# 11_RCL.net
KiCad netlist of a schematic drawn in EAGLE
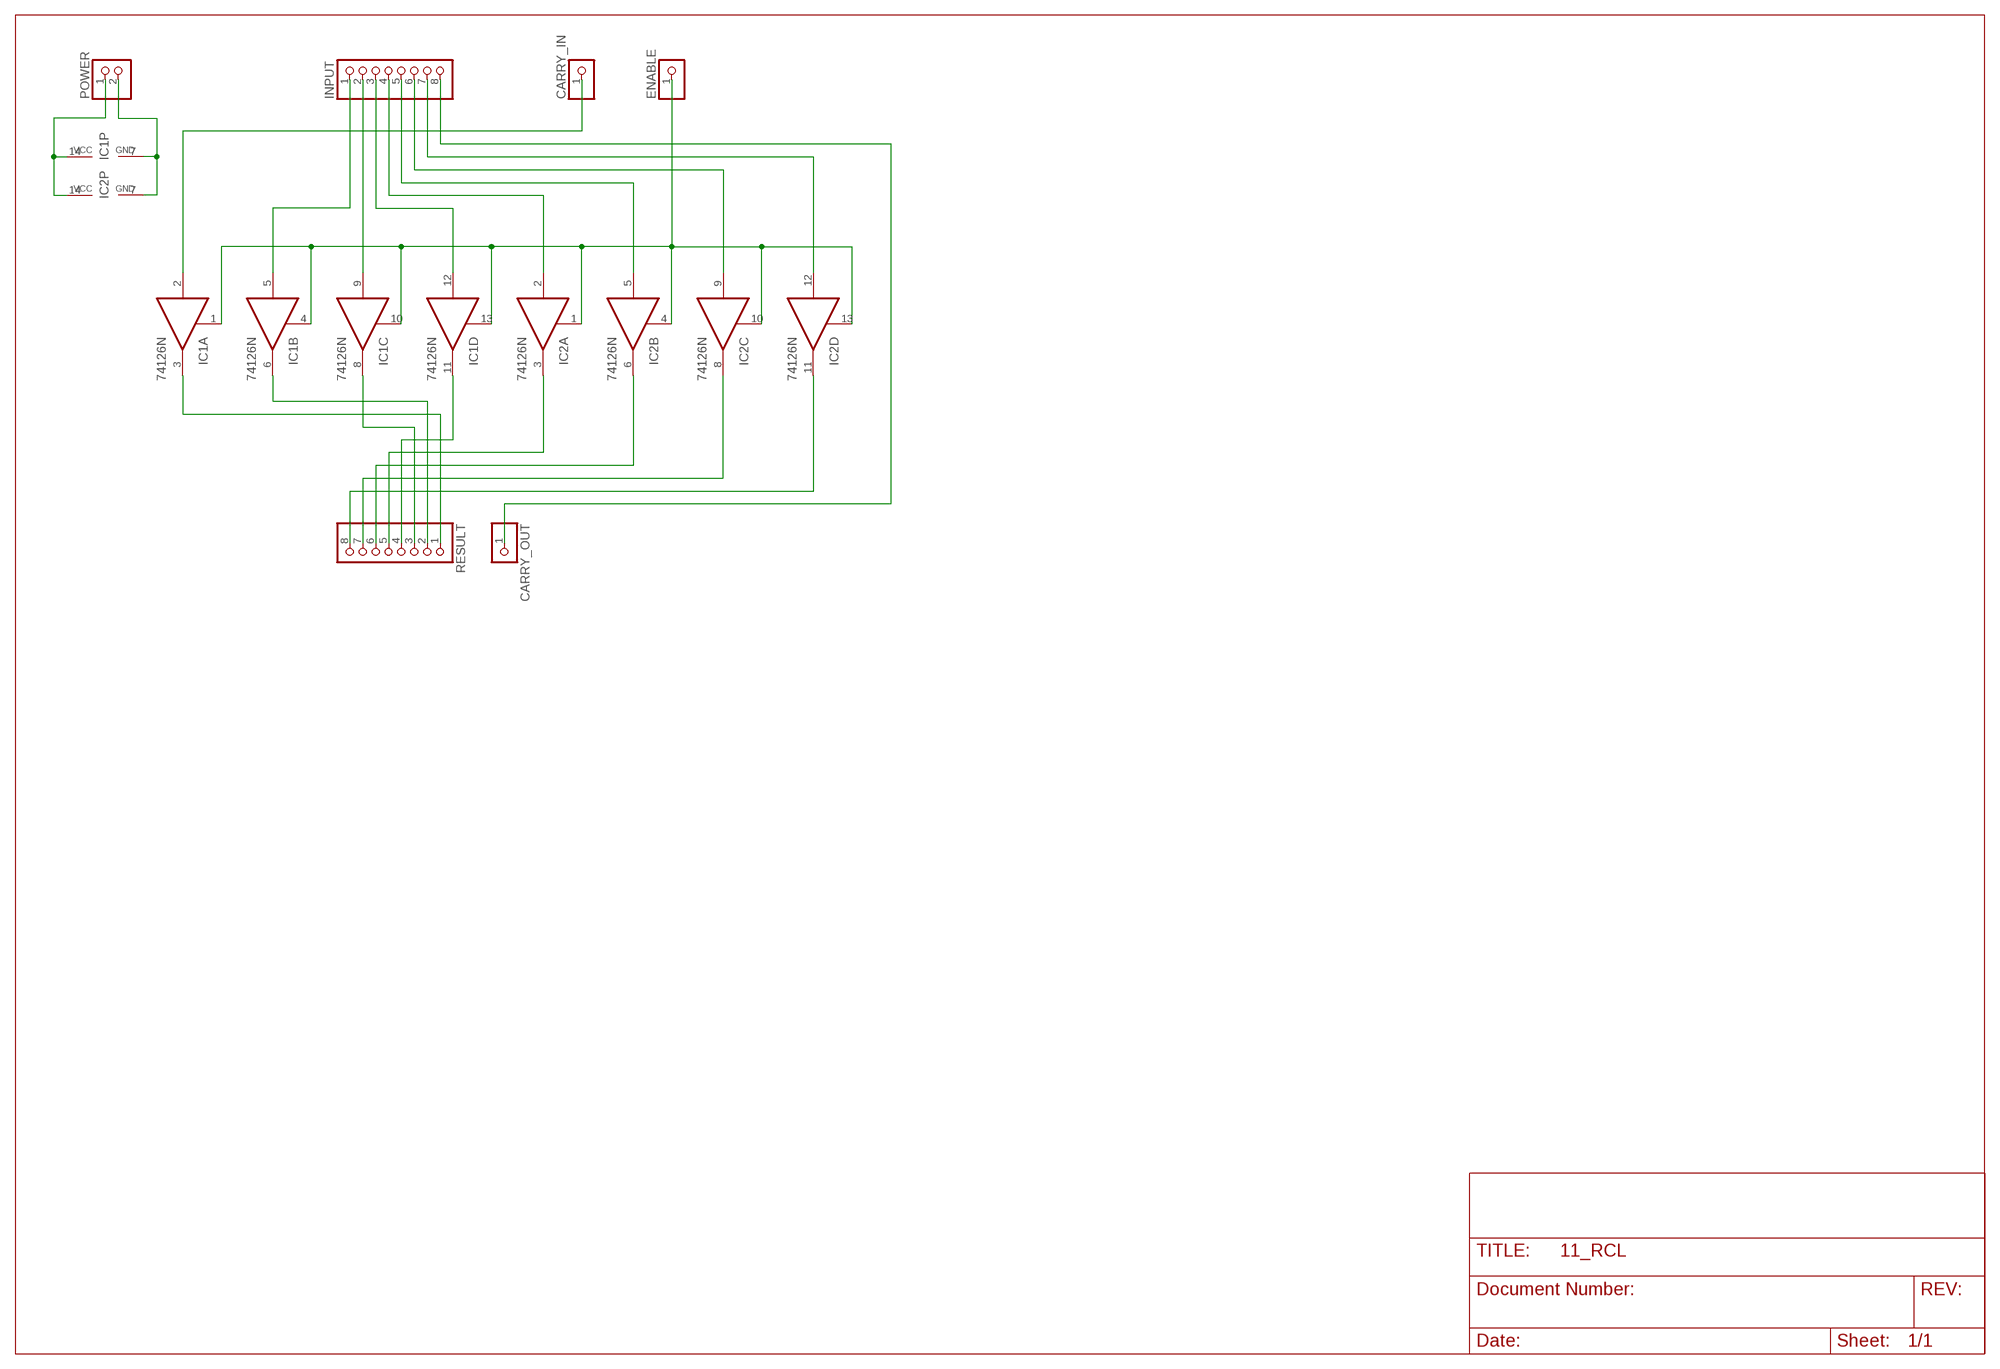
[diagram p0: schematic, sheet 1]

(export (version "E")
  (design (tool "Eeschema 10.0.6"))
  (components
    (comp (ref "CARRY_IN")
      (value "PINHD-1X1")
      (footprint "eagle-import:1X01")
      (libsource (lib "eagle-import") (part "PINHD-1X1"))
    )
    (comp (ref "CARRY_OUT")
      (value "PINHD-1X1")
      (footprint "eagle-import:1X01")
      (libsource (lib "eagle-import") (part "PINHD-1X1"))
    )
    (comp (ref "ENABLE")
      (value "PINHD-1X1")
      (footprint "eagle-import:1X01")
      (libsource (lib "eagle-import") (part "PINHD-1X1"))
    )
    (comp (ref "IC1")
      (value "74126N")
      (footprint "eagle-import:DIL14")
      (libsource (lib "eagle-import") (part "74126N"))
    )
    (comp (ref "IC2")
      (value "74126N")
      (footprint "eagle-import:DIL14")
      (libsource (lib "eagle-import") (part "74126N"))
    )
    (comp (ref "INPUT")
      (value "PINHD-1X8")
      (footprint "eagle-import:1X08")
      (libsource (lib "eagle-import") (part "PINHD-1X8"))
    )
    (comp (ref "POWER")
      (value "PINHD-1X2")
      (footprint "eagle-import:1X02")
      (libsource (lib "eagle-import") (part "PINHD-1X2"))
    )
    (comp (ref "RESULT")
      (value "PINHD-1X8")
      (footprint "eagle-import:1X08")
      (libsource (lib "eagle-import") (part "PINHD-1X8"))
    )
  )
  (nets
    (net (code "1") (name "Net-(CARRY_OUT-Pad1)") (class "Default")
      (node (ref "CARRY_OUT") (pin "1") (pinfunction "1_1") (pintype "passive"))
      (node (ref "INPUT") (pin "8") (pinfunction "8_8") (pintype "passive"))
    )
    (net (code "2") (name "Net-(IC1A-I)") (class "Default")
      (node (ref "CARRY_IN") (pin "1") (pinfunction "1_1") (pintype "passive"))
      (node (ref "IC1") (pin "2") (pinfunction "I_2") (pintype "input"))
    )
    (net (code "3") (name "Net-(IC1A-O)") (class "Default")
      (node (ref "IC1") (pin "3") (pinfunction "O_3") (pintype "output"))
      (node (ref "RESULT") (pin "1") (pinfunction "1_1") (pintype "passive"))
    )
    (net (code "4") (name "Net-(IC1A-OE)") (class "Default")
      (node (ref "ENABLE") (pin "1") (pinfunction "1_1") (pintype "passive"))
      (node (ref "IC1") (pin "1") (pinfunction "OE_1") (pintype "input"))
      (node (ref "IC1") (pin "10") (pinfunction "OE_10") (pintype "input"))
      (node (ref "IC1") (pin "13") (pinfunction "OE_13") (pintype "input"))
      (node (ref "IC1") (pin "4") (pinfunction "OE_4") (pintype "input"))
      (node (ref "IC2") (pin "1") (pinfunction "OE_1") (pintype "input"))
      (node (ref "IC2") (pin "10") (pinfunction "OE_10") (pintype "input"))
      (node (ref "IC2") (pin "13") (pinfunction "OE_13") (pintype "input"))
      (node (ref "IC2") (pin "4") (pinfunction "OE_4") (pintype "input"))
    )
    (net (code "5") (name "Net-(IC1B-I)") (class "Default")
      (node (ref "IC1") (pin "5") (pinfunction "I_5") (pintype "input"))
      (node (ref "INPUT") (pin "1") (pinfunction "1_1") (pintype "passive"))
    )
    (net (code "6") (name "Net-(IC1B-O)") (class "Default")
      (node (ref "IC1") (pin "6") (pinfunction "O_6") (pintype "output"))
      (node (ref "RESULT") (pin "2") (pinfunction "2_2") (pintype "passive"))
    )
    (net (code "7") (name "Net-(IC1C-I)") (class "Default")
      (node (ref "IC1") (pin "9") (pinfunction "I_9") (pintype "input"))
      (node (ref "INPUT") (pin "2") (pinfunction "2_2") (pintype "passive"))
    )
    (net (code "8") (name "Net-(IC1C-O)") (class "Default")
      (node (ref "IC1") (pin "8") (pinfunction "O_8") (pintype "output"))
      (node (ref "RESULT") (pin "3") (pinfunction "3_3") (pintype "passive"))
    )
    (net (code "9") (name "Net-(IC1D-I)") (class "Default")
      (node (ref "IC1") (pin "12") (pinfunction "I_12") (pintype "input"))
      (node (ref "INPUT") (pin "3") (pinfunction "3_3") (pintype "passive"))
    )
    (net (code "10") (name "Net-(IC1D-O)") (class "Default")
      (node (ref "IC1") (pin "11") (pinfunction "O_11") (pintype "output"))
      (node (ref "RESULT") (pin "4") (pinfunction "4_4") (pintype "passive"))
    )
    (net (code "11") (name "Net-(IC1E-GND)") (class "Default")
      (node (ref "IC1") (pin "7") (pinfunction "GND_7") (pintype "power_in"))
      (node (ref "IC2") (pin "7") (pinfunction "GND_7") (pintype "power_in"))
      (node (ref "POWER") (pin "2") (pinfunction "2_2") (pintype "passive"))
    )
    (net (code "12") (name "Net-(IC1E-VCC)") (class "Default")
      (node (ref "IC1") (pin "14") (pinfunction "VCC_14") (pintype "power_in"))
      (node (ref "IC2") (pin "14") (pinfunction "VCC_14") (pintype "power_in"))
      (node (ref "POWER") (pin "1") (pinfunction "1_1") (pintype "passive"))
    )
    (net (code "13") (name "Net-(IC2A-I)") (class "Default")
      (node (ref "IC2") (pin "2") (pinfunction "I_2") (pintype "input"))
      (node (ref "INPUT") (pin "4") (pinfunction "4_4") (pintype "passive"))
    )
    (net (code "14") (name "Net-(IC2A-O)") (class "Default")
      (node (ref "IC2") (pin "3") (pinfunction "O_3") (pintype "output"))
      (node (ref "RESULT") (pin "5") (pinfunction "5_5") (pintype "passive"))
    )
    (net (code "15") (name "Net-(IC2B-I)") (class "Default")
      (node (ref "IC2") (pin "5") (pinfunction "I_5") (pintype "input"))
      (node (ref "INPUT") (pin "5") (pinfunction "5_5") (pintype "passive"))
    )
    (net (code "16") (name "Net-(IC2B-O)") (class "Default")
      (node (ref "IC2") (pin "6") (pinfunction "O_6") (pintype "output"))
      (node (ref "RESULT") (pin "6") (pinfunction "6_6") (pintype "passive"))
    )
    (net (code "17") (name "Net-(IC2C-I)") (class "Default")
      (node (ref "IC2") (pin "9") (pinfunction "I_9") (pintype "input"))
      (node (ref "INPUT") (pin "6") (pinfunction "6_6") (pintype "passive"))
    )
    (net (code "18") (name "Net-(IC2C-O)") (class "Default")
      (node (ref "IC2") (pin "8") (pinfunction "O_8") (pintype "output"))
      (node (ref "RESULT") (pin "7") (pinfunction "7_7") (pintype "passive"))
    )
    (net (code "19") (name "Net-(IC2D-I)") (class "Default")
      (node (ref "IC2") (pin "12") (pinfunction "I_12") (pintype "input"))
      (node (ref "INPUT") (pin "7") (pinfunction "7_7") (pintype "passive"))
    )
    (net (code "20") (name "Net-(IC2D-O)") (class "Default")
      (node (ref "IC2") (pin "11") (pinfunction "O_11") (pintype "output"))
      (node (ref "RESULT") (pin "8") (pinfunction "8_8") (pintype "passive"))
    )
  )
)
